# FabScan-Shield_v12.net
KiCad netlist of a schematic drawn in EAGLE
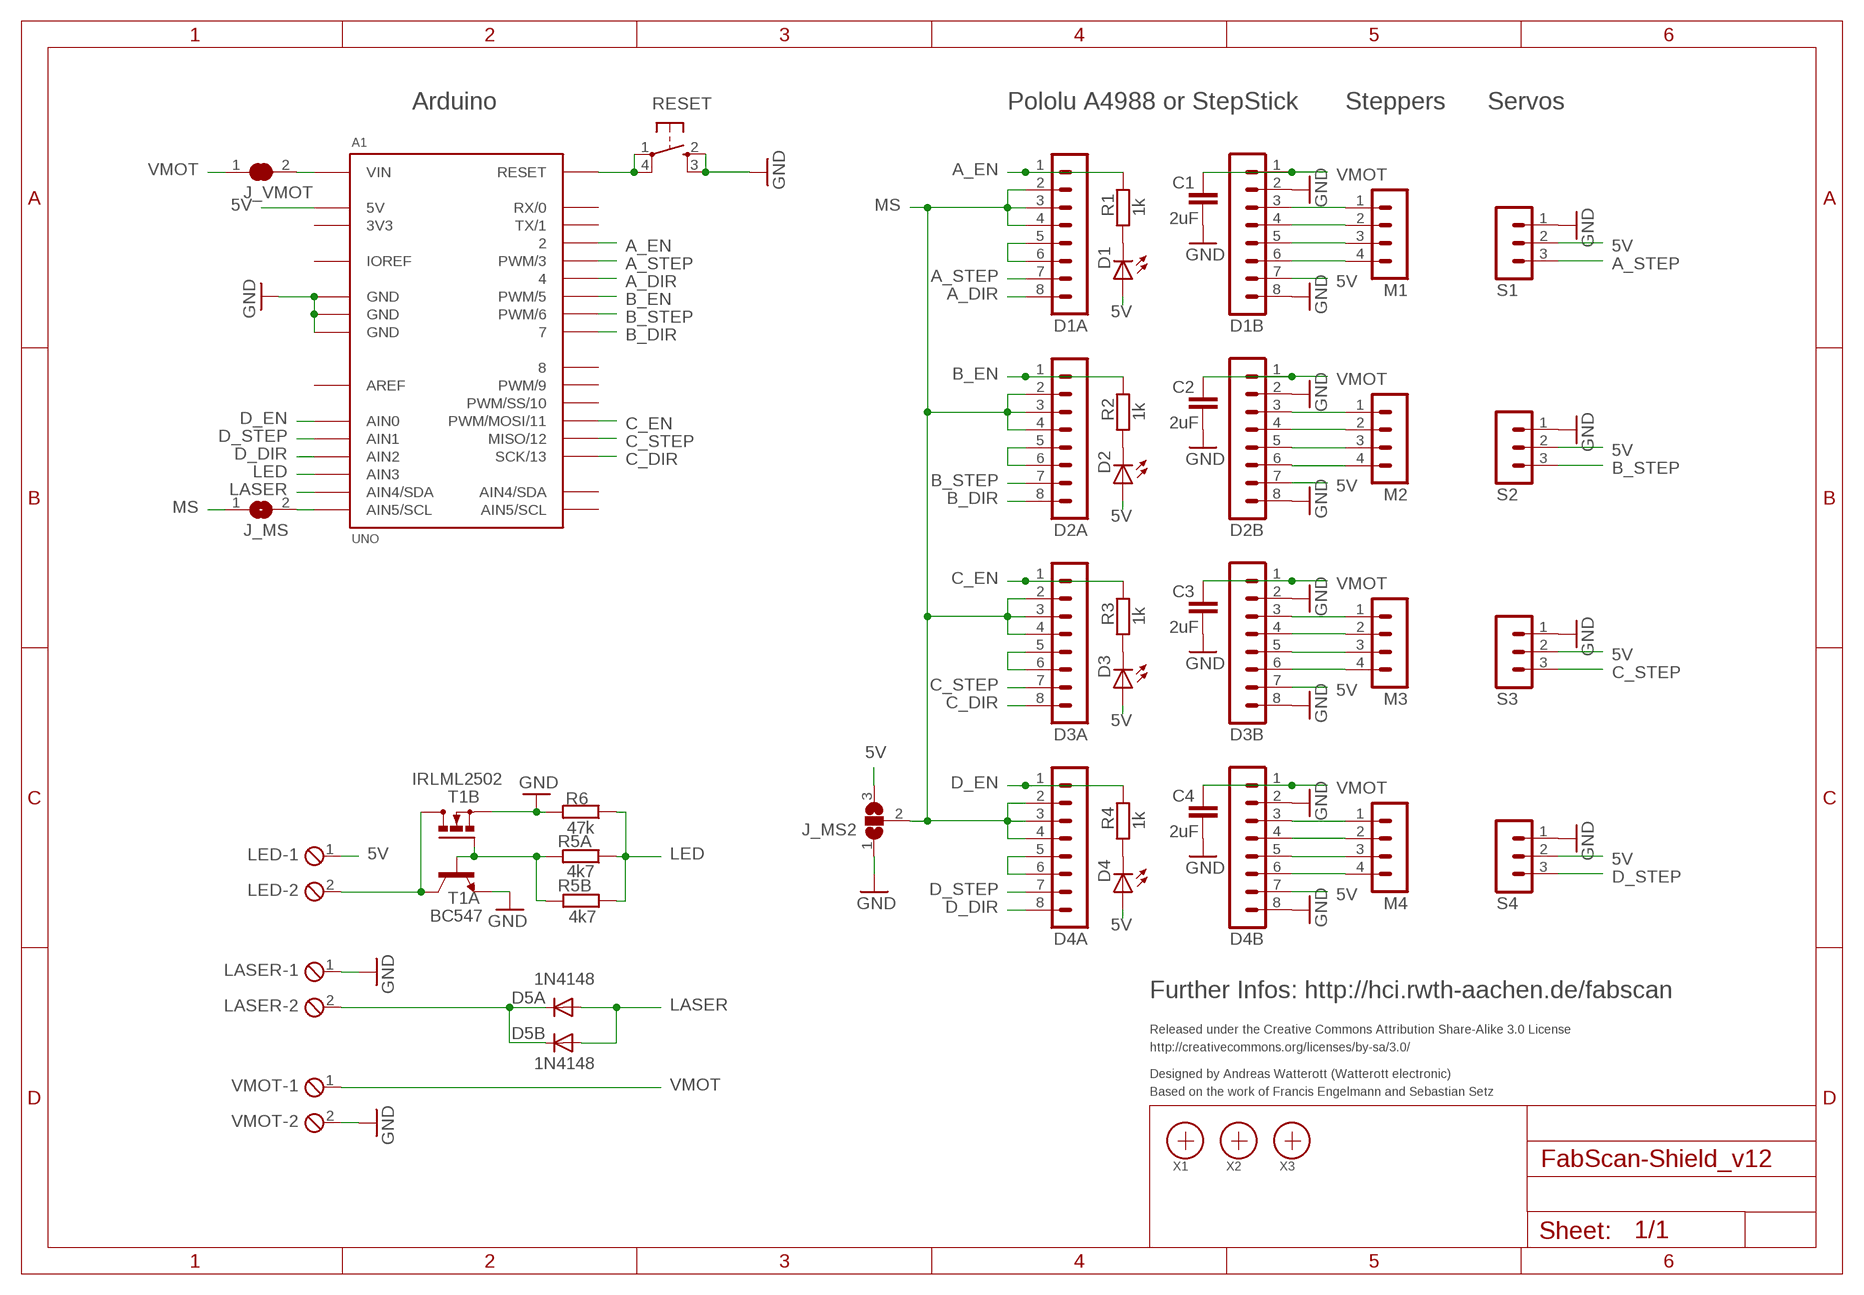
[diagram p0: schematic, sheet 1]

(export (version "E")
  (design (tool "Eeschema 10.0.6"))
  (components
    (comp (ref "A1")
      (value "UNO")
      (footprint "eagle-import:UNO")
      (libsource (lib "eagle-import") (part "UNO"))
    )
    (comp (ref "C1")
      (value "2uF")
      (footprint "eagle-import:C0603")
      (libsource (lib "eagle-import") (part "C-EUC0603"))
    )
    (comp (ref "C2")
      (value "2uF")
      (footprint "eagle-import:C0603")
      (libsource (lib "eagle-import") (part "C-EUC0603"))
    )
    (comp (ref "C3")
      (value "2uF")
      (footprint "eagle-import:C0603")
      (libsource (lib "eagle-import") (part "C-EUC0603"))
    )
    (comp (ref "C4")
      (value "2uF")
      (footprint "eagle-import:C0603")
      (libsource (lib "eagle-import") (part "C-EUC0603"))
    )
    (comp (ref "D1")
      (value "LEDCHIPLED_0603")
      (footprint "eagle-import:CHIPLED_0603")
      (libsource (lib "eagle-import") (part "LEDCHIPLED_0603"))
    )
    (comp (ref "D1A")
      (value "MA08-1")
      (footprint "eagle-import:MA08-1")
      (libsource (lib "eagle-import") (part "MA08-1"))
    )
    (comp (ref "D1B")
      (value "MA08-1")
      (footprint "eagle-import:MA08-1")
      (libsource (lib "eagle-import") (part "MA08-1"))
    )
    (comp (ref "D2")
      (value "LEDCHIPLED_0603")
      (footprint "eagle-import:CHIPLED_0603")
      (libsource (lib "eagle-import") (part "LEDCHIPLED_0603"))
    )
    (comp (ref "D2A")
      (value "MA08-1")
      (footprint "eagle-import:MA08-1")
      (libsource (lib "eagle-import") (part "MA08-1"))
    )
    (comp (ref "D2B")
      (value "MA08-1")
      (footprint "eagle-import:MA08-1")
      (libsource (lib "eagle-import") (part "MA08-1"))
    )
    (comp (ref "D3")
      (value "LEDCHIPLED_0603")
      (footprint "eagle-import:CHIPLED_0603")
      (libsource (lib "eagle-import") (part "LEDCHIPLED_0603"))
    )
    (comp (ref "D3A")
      (value "MA08-1")
      (footprint "eagle-import:MA08-1")
      (libsource (lib "eagle-import") (part "MA08-1"))
    )
    (comp (ref "D3B")
      (value "MA08-1")
      (footprint "eagle-import:MA08-1")
      (libsource (lib "eagle-import") (part "MA08-1"))
    )
    (comp (ref "D4")
      (value "LEDCHIPLED_0603")
      (footprint "eagle-import:CHIPLED_0603")
      (libsource (lib "eagle-import") (part "LEDCHIPLED_0603"))
    )
    (comp (ref "D4A")
      (value "MA08-1")
      (footprint "eagle-import:MA08-1")
      (libsource (lib "eagle-import") (part "MA08-1"))
    )
    (comp (ref "D4B")
      (value "MA08-1")
      (footprint "eagle-import:MA08-1")
      (libsource (lib "eagle-import") (part "MA08-1"))
    )
    (comp (ref "D5A")
      (value "1N4148")
      (footprint "eagle-import:DO35-7")
      (libsource (lib "eagle-import") (part "1N4148DO35-7"))
    )
    (comp (ref "D5B")
      (value "1N4148")
      (footprint "eagle-import:SOD106-R")
      (libsource (lib "eagle-import") (part "DIODE-SOD106-R"))
    )
    (comp (ref "J_MS")
      (value "SJ")
      (footprint "eagle-import:SJ")
      (libsource (lib "eagle-import") (part "SJ"))
    )
    (comp (ref "J_MS2")
      (value "SJ2W")
      (footprint "eagle-import:SJ_2")
      (libsource (lib "eagle-import") (part "SJ2W"))
    )
    (comp (ref "J_VMOT")
      (value "SJ")
      (footprint "eagle-import:SJ")
      (libsource (lib "eagle-import") (part "SJ"))
    )
    (comp (ref "LASER")
      (value "MPT2")
      (footprint "eagle-import:2POL254")
      (fields (field (name "OC_FARNELL") "unknown") (field (name "OC_NEWARK") "unknown"))
      (libsource (lib "eagle-import") (part "MPT2"))
    )
    (comp (ref "LED")
      (value "MPT2")
      (footprint "eagle-import:2POL254")
      (libsource (lib "eagle-import") (part "MPT2"))
    )
    (comp (ref "M1")
      (value "MA04-1")
      (footprint "eagle-import:MA04-1")
      (libsource (lib "eagle-import") (part "MA04-1"))
    )
    (comp (ref "M2")
      (value "MA04-1")
      (footprint "eagle-import:MA04-1")
      (fields (field (name "OC_FARNELL") "unknown") (field (name "OC_NEWARK") "unknown"))
      (libsource (lib "eagle-import") (part "MA04-1"))
    )
    (comp (ref "M3")
      (value "MA04-1")
      (footprint "eagle-import:MA04-1")
      (fields (field (name "OC_FARNELL") "unknown") (field (name "OC_NEWARK") "unknown"))
      (libsource (lib "eagle-import") (part "MA04-1"))
    )
    (comp (ref "M4")
      (value "MA04-1")
      (footprint "eagle-import:MA04-1")
      (fields (field (name "OC_FARNELL") "unknown") (field (name "OC_NEWARK") "unknown"))
      (libsource (lib "eagle-import") (part "MA04-1"))
    )
    (comp (ref "R1")
      (value "1k")
      (footprint "eagle-import:R0603")
      (libsource (lib "eagle-import") (part "R-EU_R0603"))
    )
    (comp (ref "R2")
      (value "1k")
      (footprint "eagle-import:R0603")
      (libsource (lib "eagle-import") (part "R-EU_R0603"))
    )
    (comp (ref "R3")
      (value "1k")
      (footprint "eagle-import:R0603")
      (libsource (lib "eagle-import") (part "R-EU_R0603"))
    )
    (comp (ref "R4")
      (value "1k")
      (footprint "eagle-import:R0603")
      (libsource (lib "eagle-import") (part "R-EU_R0603"))
    )
    (comp (ref "R5A")
      (value "4k7")
      (footprint "eagle-import:0204_7")
      (libsource (lib "eagle-import") (part "R-EU_0204/7"))
    )
    (comp (ref "R5B")
      (value "4k7")
      (footprint "eagle-import:R0603")
      (libsource (lib "eagle-import") (part "R-EU_R0603"))
    )
    (comp (ref "R6")
      (value "47k")
      (footprint "eagle-import:R0603")
      (libsource (lib "eagle-import") (part "R-EU_R0603"))
    )
    (comp (ref "RESET")
      (value "SW_SMDS")
      (footprint "eagle-import:SW_SMD4")
      (libsource (lib "eagle-import") (part "SW_SMDS"))
    )
    (comp (ref "S1")
      (value "MA03-1")
      (footprint "eagle-import:MA03-1")
      (libsource (lib "eagle-import") (part "MA03-1"))
    )
    (comp (ref "S2")
      (value "MA03-1")
      (footprint "eagle-import:MA03-1")
      (libsource (lib "eagle-import") (part "MA03-1"))
    )
    (comp (ref "S3")
      (value "MA03-1")
      (footprint "eagle-import:MA03-1")
      (libsource (lib "eagle-import") (part "MA03-1"))
    )
    (comp (ref "S4")
      (value "MA03-1")
      (footprint "eagle-import:MA03-1")
      (libsource (lib "eagle-import") (part "MA03-1"))
    )
    (comp (ref "T1A")
      (value "BC547")
      (footprint "eagle-import:TO92")
      (libsource (lib "eagle-import") (part "BC547"))
    )
    (comp (ref "T1B")
      (value "IRLML2502")
      (footprint "eagle-import:MICRO3")
      (libsource (lib "eagle-import") (part "IRLML2502"))
    )
    (comp (ref "VMOT")
      (value "MPT2")
      (footprint "eagle-import:2POL254")
      (fields (field (name "OC_FARNELL") "unknown") (field (name "OC_NEWARK") "unknown"))
      (libsource (lib "eagle-import") (part "MPT2"))
    )
    (comp (ref "X1")
      (value "PASSER")
      (footprint "eagle-import:PASSER")
      (libsource (lib "eagle-import") (part "PASSER"))
    )
    (comp (ref "X2")
      (value "PASSER")
      (footprint "eagle-import:PASSER")
      (libsource (lib "eagle-import") (part "PASSER"))
    )
    (comp (ref "X3")
      (value "PASSER")
      (footprint "eagle-import:PASSER")
      (libsource (lib "eagle-import") (part "PASSER"))
    )
  )
  (nets
    (net (code "1") (name "/3V3") (class "Default")
      (node (ref "A1") (pin "3V3") (pinfunction "3V3_3V3") (pintype "power_in"))
    )
    (net (code "2") (name "/5V") (class "Default")
      (node (ref "A1") (pin "5V") (pinfunction "5V_5V") (pintype "power_in"))
      (node (ref "D1") (pin "A") (pinfunction "A_A") (pintype "passive"))
      (node (ref "D1B") (pin "7") (pinfunction "7_7") (pintype "passive"))
      (node (ref "D2") (pin "A") (pinfunction "A_A") (pintype "passive"))
      (node (ref "D2B") (pin "7") (pinfunction "7_7") (pintype "passive"))
      (node (ref "D3") (pin "A") (pinfunction "A_A") (pintype "passive"))
      (node (ref "D3B") (pin "7") (pinfunction "7_7") (pintype "passive"))
      (node (ref "D4") (pin "A") (pinfunction "A_A") (pintype "passive"))
      (node (ref "D4B") (pin "7") (pinfunction "7_7") (pintype "passive"))
      (node (ref "J_MS2") (pin "3") (pinfunction "3_3") (pintype "passive"))
      (node (ref "LED") (pin "1") (pinfunction "1_1") (pintype "passive"))
      (node (ref "S1") (pin "2") (pinfunction "2_2") (pintype "passive"))
      (node (ref "S2") (pin "2") (pinfunction "2_2") (pintype "passive"))
      (node (ref "S3") (pin "2") (pinfunction "2_2") (pintype "passive"))
      (node (ref "S4") (pin "2") (pinfunction "2_2") (pintype "passive"))
    )
    (net (code "3") (name "/AREF") (class "Default")
      (node (ref "A1") (pin "AREF") (pinfunction "AREF_AREF") (pintype "power_in"))
    )
    (net (code "4") (name "/A_DIR") (class "Default")
      (node (ref "A1") (pin "4") (pinfunction "4_4") (pintype "bidirectional"))
      (node (ref "D1A") (pin "8") (pinfunction "8_8") (pintype "passive"))
    )
    (net (code "5") (name "/A_EN") (class "Default")
      (node (ref "A1") (pin "2") (pinfunction "2_2") (pintype "bidirectional"))
      (node (ref "D1A") (pin "1") (pinfunction "1_1") (pintype "passive"))
      (node (ref "R1") (pin "1") (pinfunction "1_1") (pintype "passive"))
    )
    (net (code "6") (name "/A_STEP") (class "Default")
      (node (ref "A1") (pin "3") (pinfunction "PWM/3_3") (pintype "bidirectional"))
      (node (ref "D1A") (pin "7") (pinfunction "7_7") (pintype "passive"))
      (node (ref "S1") (pin "3") (pinfunction "3_3") (pintype "passive"))
    )
    (net (code "7") (name "/B_DIR") (class "Default")
      (node (ref "A1") (pin "7") (pinfunction "7_7") (pintype "bidirectional"))
      (node (ref "D2A") (pin "8") (pinfunction "8_8") (pintype "passive"))
    )
    (net (code "8") (name "/B_EN") (class "Default")
      (node (ref "A1") (pin "5") (pinfunction "PWM/5_5") (pintype "bidirectional"))
      (node (ref "D2A") (pin "1") (pinfunction "1_1") (pintype "passive"))
      (node (ref "R2") (pin "1") (pinfunction "1_1") (pintype "passive"))
    )
    (net (code "9") (name "/B_STEP") (class "Default")
      (node (ref "A1") (pin "6") (pinfunction "PWM/6_6") (pintype "bidirectional"))
      (node (ref "D2A") (pin "7") (pinfunction "7_7") (pintype "passive"))
      (node (ref "S2") (pin "3") (pinfunction "3_3") (pintype "passive"))
    )
    (net (code "10") (name "/C_DIR") (class "Default")
      (node (ref "A1") (pin "13") (pinfunction "SCK/13_13") (pintype "bidirectional"))
      (node (ref "D3A") (pin "8") (pinfunction "8_8") (pintype "passive"))
    )
    (net (code "11") (name "/C_EN") (class "Default")
      (node (ref "A1") (pin "11") (pinfunction "PWM/MOSI/11_11") (pintype "bidirectional"))
      (node (ref "D3A") (pin "1") (pinfunction "1_1") (pintype "passive"))
      (node (ref "R3") (pin "1") (pinfunction "1_1") (pintype "passive"))
    )
    (net (code "12") (name "/C_STEP") (class "Default")
      (node (ref "A1") (pin "12") (pinfunction "MISO/12_12") (pintype "bidirectional"))
      (node (ref "D3A") (pin "7") (pinfunction "7_7") (pintype "passive"))
      (node (ref "S3") (pin "3") (pinfunction "3_3") (pintype "passive"))
    )
    (net (code "13") (name "/D_DIR") (class "Default")
      (node (ref "A1") (pin "AIN2") (pinfunction "AIN2_AIN2") (pintype "bidirectional"))
      (node (ref "D4A") (pin "8") (pinfunction "8_8") (pintype "passive"))
    )
    (net (code "14") (name "/D_EN") (class "Default")
      (node (ref "A1") (pin "AIN0") (pinfunction "AIN0_AIN0") (pintype "bidirectional"))
      (node (ref "D4A") (pin "1") (pinfunction "1_1") (pintype "passive"))
      (node (ref "R4") (pin "1") (pinfunction "1_1") (pintype "passive"))
    )
    (net (code "15") (name "/D_STEP") (class "Default")
      (node (ref "A1") (pin "AIN1") (pinfunction "AIN1_AIN1") (pintype "bidirectional"))
      (node (ref "D4A") (pin "7") (pinfunction "7_7") (pintype "passive"))
      (node (ref "S4") (pin "3") (pinfunction "3_3") (pintype "passive"))
    )
    (net (code "16") (name "/IOREF") (class "Default")
      (node (ref "A1") (pin "IOREF") (pinfunction "IOREF_IOREF") (pintype "power_in"))
    )
    (net (code "17") (name "/LASER") (class "Default")
      (node (ref "A1") (pin "AIN4") (pinfunction "AIN4/SDA_AIN4") (pintype "bidirectional"))
      (node (ref "D5A") (pin "A") (pinfunction "A_A") (pintype "passive"))
      (node (ref "D5B") (pin "A") (pinfunction "A_A") (pintype "passive"))
    )
    (net (code "18") (name "/LED") (class "Default")
      (node (ref "A1") (pin "AIN3") (pinfunction "AIN3_AIN3") (pintype "bidirectional"))
      (node (ref "R5A") (pin "1") (pinfunction "1_1") (pintype "passive"))
      (node (ref "R5B") (pin "2") (pinfunction "2_2") (pintype "passive"))
      (node (ref "R6") (pin "1") (pinfunction "1_1") (pintype "passive"))
    )
    (net (code "19") (name "/MS") (class "Default")
      (node (ref "D1A") (pin "2") (pinfunction "2_2") (pintype "passive"))
      (node (ref "D1A") (pin "3") (pinfunction "3_3") (pintype "passive"))
      (node (ref "D1A") (pin "4") (pinfunction "4_4") (pintype "passive"))
      (node (ref "D2A") (pin "2") (pinfunction "2_2") (pintype "passive"))
      (node (ref "D2A") (pin "3") (pinfunction "3_3") (pintype "passive"))
      (node (ref "D2A") (pin "4") (pinfunction "4_4") (pintype "passive"))
      (node (ref "D3A") (pin "2") (pinfunction "2_2") (pintype "passive"))
      (node (ref "D3A") (pin "3") (pinfunction "3_3") (pintype "passive"))
      (node (ref "D3A") (pin "4") (pinfunction "4_4") (pintype "passive"))
      (node (ref "D4A") (pin "2") (pinfunction "2_2") (pintype "passive"))
      (node (ref "D4A") (pin "3") (pinfunction "3_3") (pintype "passive"))
      (node (ref "D4A") (pin "4") (pinfunction "4_4") (pintype "passive"))
      (node (ref "J_MS") (pin "1") (pinfunction "1_1") (pintype "passive"))
      (node (ref "J_MS2") (pin "2") (pinfunction "2_2") (pintype "passive"))
    )
    (net (code "20") (name "/VMOT") (class "Default")
      (node (ref "C1") (pin "1") (pinfunction "1_1") (pintype "passive"))
      (node (ref "C2") (pin "1") (pinfunction "1_1") (pintype "passive"))
      (node (ref "C3") (pin "1") (pinfunction "1_1") (pintype "passive"))
      (node (ref "C4") (pin "1") (pinfunction "1_1") (pintype "passive"))
      (node (ref "D1B") (pin "1") (pinfunction "1_1") (pintype "passive"))
      (node (ref "D2B") (pin "1") (pinfunction "1_1") (pintype "passive"))
      (node (ref "D3B") (pin "1") (pinfunction "1_1") (pintype "passive"))
      (node (ref "D4B") (pin "1") (pinfunction "1_1") (pintype "passive"))
      (node (ref "J_VMOT") (pin "1") (pinfunction "1_1") (pintype "passive"))
      (node (ref "VMOT") (pin "1") (pinfunction "1_1") (pintype "passive"))
    )
    (net (code "21") (name "GND") (class "Default")
      (node (ref "A1") (pin "GND@1") (pinfunction "GND_GND@1") (pintype "power_in"))
      (node (ref "A1") (pin "GND@2") (pinfunction "GND_GND@2") (pintype "power_in"))
      (node (ref "A1") (pin "GND@3") (pinfunction "GND_GND@3") (pintype "power_in"))
      (node (ref "C1") (pin "2") (pinfunction "2_2") (pintype "passive"))
      (node (ref "C2") (pin "2") (pinfunction "2_2") (pintype "passive"))
      (node (ref "C3") (pin "2") (pinfunction "2_2") (pintype "passive"))
      (node (ref "C4") (pin "2") (pinfunction "2_2") (pintype "passive"))
      (node (ref "D1B") (pin "2") (pinfunction "2_2") (pintype "passive"))
      (node (ref "D1B") (pin "8") (pinfunction "8_8") (pintype "passive"))
      (node (ref "D2B") (pin "2") (pinfunction "2_2") (pintype "passive"))
      (node (ref "D2B") (pin "8") (pinfunction "8_8") (pintype "passive"))
      (node (ref "D3B") (pin "2") (pinfunction "2_2") (pintype "passive"))
      (node (ref "D3B") (pin "8") (pinfunction "8_8") (pintype "passive"))
      (node (ref "D4B") (pin "2") (pinfunction "2_2") (pintype "passive"))
      (node (ref "D4B") (pin "8") (pinfunction "8_8") (pintype "passive"))
      (node (ref "J_MS2") (pin "1") (pinfunction "1_1") (pintype "passive"))
      (node (ref "LASER") (pin "1") (pinfunction "1_1") (pintype "passive"))
      (node (ref "R6") (pin "2") (pinfunction "2_2") (pintype "passive"))
      (node (ref "RESET") (pin "2") (pinfunction "S_2") (pintype "passive"))
      (node (ref "RESET") (pin "3") (pinfunction "S1_3") (pintype "passive"))
      (node (ref "S1") (pin "1") (pinfunction "1_1") (pintype "passive"))
      (node (ref "S2") (pin "1") (pinfunction "1_1") (pintype "passive"))
      (node (ref "S3") (pin "1") (pinfunction "1_1") (pintype "passive"))
      (node (ref "S4") (pin "1") (pinfunction "1_1") (pintype "passive"))
      (node (ref "T1A") (pin "1") (pinfunction "E_1") (pintype "passive"))
      (node (ref "T1B") (pin "2") (pinfunction "S_2") (pintype "passive"))
      (node (ref "VMOT") (pin "2") (pinfunction "1_2") (pintype "passive"))
    )
    (net (code "22") (name "Net-(A1-AIN5{slash}SCL-PadAIN5)") (class "Default")
      (node (ref "A1") (pin "AIN5") (pinfunction "AIN5/SCL_AIN5") (pintype "bidirectional"))
      (node (ref "J_MS") (pin "2") (pinfunction "2_2") (pintype "passive"))
    )
    (net (code "23") (name "Net-(A1-PadVIN)") (class "Default")
      (node (ref "A1") (pin "VIN") (pinfunction "VIN_VIN") (pintype "power_in"))
      (node (ref "J_VMOT") (pin "2") (pinfunction "2_2") (pintype "passive"))
    )
    (net (code "24") (name "Net-(A1-RESET)") (class "Default")
      (node (ref "A1") (pin "RST") (pinfunction "RESET_RST") (pintype "bidirectional"))
      (node (ref "RESET") (pin "1") (pinfunction "P_1") (pintype "passive"))
      (node (ref "RESET") (pin "4") (pinfunction "P1_4") (pintype "passive"))
    )
    (net (code "25") (name "Net-(D1-PadC)") (class "Default")
      (node (ref "D1") (pin "C") (pinfunction "C_C") (pintype "passive"))
      (node (ref "R1") (pin "2") (pinfunction "2_2") (pintype "passive"))
    )
    (net (code "26") (name "Net-(D1A-Pad5)") (class "Default")
      (node (ref "D1A") (pin "5") (pinfunction "5_5") (pintype "passive"))
      (node (ref "D1A") (pin "6") (pinfunction "6_6") (pintype "passive"))
    )
    (net (code "27") (name "Net-(D1B-Pad3)") (class "Default")
      (node (ref "D1B") (pin "3") (pinfunction "3_3") (pintype "passive"))
      (node (ref "M1") (pin "1") (pinfunction "1_1") (pintype "passive"))
    )
    (net (code "28") (name "Net-(D1B-Pad4)") (class "Default")
      (node (ref "D1B") (pin "4") (pinfunction "4_4") (pintype "passive"))
      (node (ref "M1") (pin "2") (pinfunction "2_2") (pintype "passive"))
    )
    (net (code "29") (name "Net-(D1B-Pad5)") (class "Default")
      (node (ref "D1B") (pin "5") (pinfunction "5_5") (pintype "passive"))
      (node (ref "M1") (pin "3") (pinfunction "3_3") (pintype "passive"))
    )
    (net (code "30") (name "Net-(D1B-Pad6)") (class "Default")
      (node (ref "D1B") (pin "6") (pinfunction "6_6") (pintype "passive"))
      (node (ref "M1") (pin "4") (pinfunction "4_4") (pintype "passive"))
    )
    (net (code "31") (name "Net-(D2-PadC)") (class "Default")
      (node (ref "D2") (pin "C") (pinfunction "C_C") (pintype "passive"))
      (node (ref "R2") (pin "2") (pinfunction "2_2") (pintype "passive"))
    )
    (net (code "32") (name "Net-(D2A-Pad5)") (class "Default")
      (node (ref "D2A") (pin "5") (pinfunction "5_5") (pintype "passive"))
      (node (ref "D2A") (pin "6") (pinfunction "6_6") (pintype "passive"))
    )
    (net (code "33") (name "Net-(D2B-Pad3)") (class "Default")
      (node (ref "D2B") (pin "3") (pinfunction "3_3") (pintype "passive"))
      (node (ref "M2") (pin "1") (pinfunction "1_1") (pintype "passive"))
    )
    (net (code "34") (name "Net-(D2B-Pad4)") (class "Default")
      (node (ref "D2B") (pin "4") (pinfunction "4_4") (pintype "passive"))
      (node (ref "M2") (pin "2") (pinfunction "2_2") (pintype "passive"))
    )
    (net (code "35") (name "Net-(D2B-Pad5)") (class "Default")
      (node (ref "D2B") (pin "5") (pinfunction "5_5") (pintype "passive"))
      (node (ref "M2") (pin "3") (pinfunction "3_3") (pintype "passive"))
    )
    (net (code "36") (name "Net-(D2B-Pad6)") (class "Default")
      (node (ref "D2B") (pin "6") (pinfunction "6_6") (pintype "passive"))
      (node (ref "M2") (pin "4") (pinfunction "4_4") (pintype "passive"))
    )
    (net (code "37") (name "Net-(D3-PadC)") (class "Default")
      (node (ref "D3") (pin "C") (pinfunction "C_C") (pintype "passive"))
      (node (ref "R3") (pin "2") (pinfunction "2_2") (pintype "passive"))
    )
    (net (code "38") (name "Net-(D3A-Pad5)") (class "Default")
      (node (ref "D3A") (pin "5") (pinfunction "5_5") (pintype "passive"))
      (node (ref "D3A") (pin "6") (pinfunction "6_6") (pintype "passive"))
    )
    (net (code "39") (name "Net-(D3B-Pad3)") (class "Default")
      (node (ref "D3B") (pin "3") (pinfunction "3_3") (pintype "passive"))
      (node (ref "M3") (pin "1") (pinfunction "1_1") (pintype "passive"))
    )
    (net (code "40") (name "Net-(D3B-Pad4)") (class "Default")
      (node (ref "D3B") (pin "4") (pinfunction "4_4") (pintype "passive"))
      (node (ref "M3") (pin "2") (pinfunction "2_2") (pintype "passive"))
    )
    (net (code "41") (name "Net-(D3B-Pad5)") (class "Default")
      (node (ref "D3B") (pin "5") (pinfunction "5_5") (pintype "passive"))
      (node (ref "M3") (pin "3") (pinfunction "3_3") (pintype "passive"))
    )
    (net (code "42") (name "Net-(D3B-Pad6)") (class "Default")
      (node (ref "D3B") (pin "6") (pinfunction "6_6") (pintype "passive"))
      (node (ref "M3") (pin "4") (pinfunction "4_4") (pintype "passive"))
    )
    (net (code "43") (name "Net-(D4-PadC)") (class "Default")
      (node (ref "D4") (pin "C") (pinfunction "C_C") (pintype "passive"))
      (node (ref "R4") (pin "2") (pinfunction "2_2") (pintype "passive"))
    )
    (net (code "44") (name "Net-(D4A-Pad5)") (class "Default")
      (node (ref "D4A") (pin "5") (pinfunction "5_5") (pintype "passive"))
      (node (ref "D4A") (pin "6") (pinfunction "6_6") (pintype "passive"))
    )
    (net (code "45") (name "Net-(D4B-Pad3)") (class "Default")
      (node (ref "D4B") (pin "3") (pinfunction "3_3") (pintype "passive"))
      (node (ref "M4") (pin "1") (pinfunction "1_1") (pintype "passive"))
    )
    (net (code "46") (name "Net-(D4B-Pad4)") (class "Default")
      (node (ref "D4B") (pin "4") (pinfunction "4_4") (pintype "passive"))
      (node (ref "M4") (pin "2") (pinfunction "2_2") (pintype "passive"))
    )
    (net (code "47") (name "Net-(D4B-Pad5)") (class "Default")
      (node (ref "D4B") (pin "5") (pinfunction "5_5") (pintype "passive"))
      (node (ref "M4") (pin "3") (pinfunction "3_3") (pintype "passive"))
    )
    (net (code "48") (name "Net-(D4B-Pad6)") (class "Default")
      (node (ref "D4B") (pin "6") (pinfunction "6_6") (pintype "passive"))
      (node (ref "M4") (pin "4") (pinfunction "4_4") (pintype "passive"))
    )
    (net (code "49") (name "Net-(LASERB-1)") (class "Default")
      (node (ref "D5A") (pin "C") (pinfunction "C_C") (pintype "passive"))
      (node (ref "D5B") (pin "C") (pinfunction "C_C") (pintype "passive"))
      (node (ref "LASER") (pin "2") (pinfunction "1_2") (pintype "passive"))
    )
    (net (code "50") (name "Net-(LEDB-1)") (class "Default")
      (node (ref "LED") (pin "2") (pinfunction "1_2") (pintype "passive"))
      (node (ref "T1A") (pin "3") (pinfunction "C_3") (pintype "passive"))
      (node (ref "T1B") (pin "3") (pinfunction "D_3") (pintype "passive"))
    )
    (net (code "51") (name "Net-(T1A-B)") (class "Default")
      (node (ref "R5A") (pin "2") (pinfunction "2_2") (pintype "passive"))
      (node (ref "R5B") (pin "1") (pinfunction "1_1") (pintype "passive"))
      (node (ref "T1A") (pin "2") (pinfunction "B_2") (pintype "passive"))
      (node (ref "T1B") (pin "1") (pinfunction "G_1") (pintype "passive"))
    )
    (net (code "52") (name "unconnected-(A1-AIN4{slash}SDA-PadSDA)") (class "Default")
      (node (ref "A1") (pin "SDA") (pinfunction "AIN4/SDA_SDA") (pintype "bidirectional"))
    )
    (net (code "53") (name "unconnected-(A1-AIN5{slash}SCL-PadSCL)") (class "Default")
      (node (ref "A1") (pin "SCL") (pinfunction "AIN5/SCL_SCL") (pintype "bidirectional"))
    )
    (net (code "54") (name "unconnected-(A1-PWM{slash}9-Pad9)") (class "Default")
      (node (ref "A1") (pin "9") (pinfunction "PWM/9_9") (pintype "bidirectional"))
    )
    (net (code "55") (name "unconnected-(A1-PWM{slash}SS{slash}10-Pad10)") (class "Default")
      (node (ref "A1") (pin "10") (pinfunction "PWM/SS/10_10") (pintype "bidirectional"))
    )
    (net (code "56") (name "unconnected-(A1-Pad8)") (class "Default")
      (node (ref "A1") (pin "8") (pinfunction "8_8") (pintype "bidirectional"))
    )
    (net (code "57") (name "unconnected-(A1-RX{slash}0-Pad0)") (class "Default")
      (node (ref "A1") (pin "0") (pinfunction "RX/0_0") (pintype "bidirectional"))
    )
    (net (code "58") (name "unconnected-(A1-TX{slash}1-Pad1)") (class "Default")
      (node (ref "A1") (pin "1") (pinfunction "TX/1_1") (pintype "bidirectional"))
    )
  )
)
